# Digital_Io.net
KiCad netlist of a schematic drawn in Altium Designer
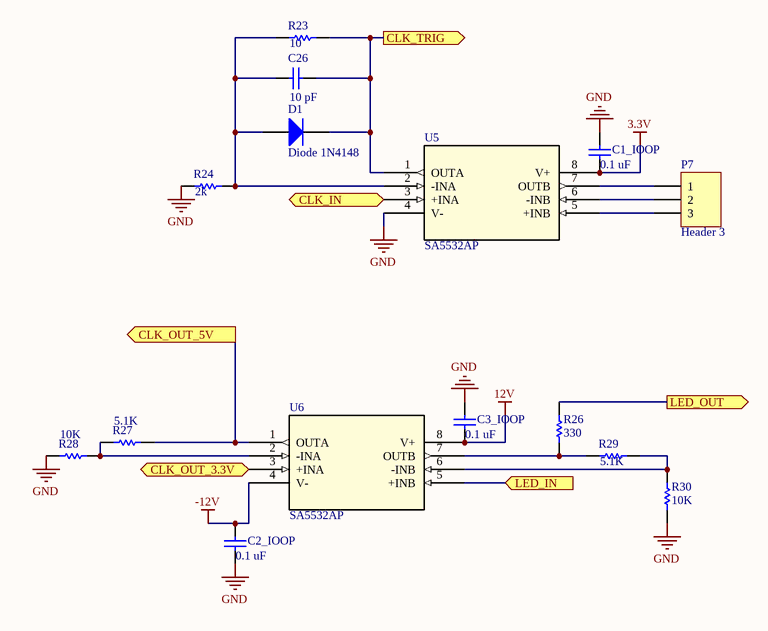
[diagram p0: Digital_Io.SchDoc]

(export (version "E")
  (design (tool "Eeschema 10.0.6"))
  (components
    (comp (ref "C1_IOOP")
      (value "0.1 uF")
      (footprint "C0805")
      (description "Capacitor")
      (fields (field (name "PUBLISHER") "Altium Limited"))
      (libsource (lib "Miscellaneous Devices") (part "Cap"))
    )
    (comp (ref "C2_IOOP")
      (value "0.1 uF")
      (footprint "C0805")
      (description "Capacitor")
      (fields (field (name "PUBLISHER") "Altium Limited"))
      (libsource (lib "Miscellaneous Devices") (part "Cap"))
    )
    (comp (ref "C3_IOOP")
      (value "0.1 uF")
      (footprint "C0805")
      (description "Capacitor")
      (fields (field (name "PUBLISHER") "Altium Limited"))
      (libsource (lib "Miscellaneous Devices") (part "Cap"))
    )
    (comp (ref "C26")
      (value "10 pF")
      (footprint "C0805")
      (description "Capacitor")
      (fields (field (name "PUBLISHER") "Altium Limited"))
      (libsource (lib "Miscellaneous Devices") (part "Cap"))
    )
    (comp (ref "D1")
      (value "Diode 1N4148")
      (footprint "DO-35")
      (description "High Conductance Fast Diode")
      (fields (field (name "PUBLISHER") "Altium Limited"))
      (libsource (lib "Miscellaneous Devices") (part "Diode 1N4148"))
    )
    (comp (ref "P7")
      (value "Header 3")
      (footprint "HDR1X3")
      (description "Header, 3-Pin")
      (fields (field (name "PUBLISHER") "Altium Limited"))
      (libsource (lib "Miscellaneous Connectors") (part "Header 3"))
    )
    (comp (ref "R23")
      (value "10")
      (footprint "AXIAL-0.3")
      (description "Resistor")
      (fields (field (name "Comment") "Res1") (field (name "PUBLISHER") "Altium Limited"))
      (libsource (lib "Miscellaneous Devices") (part "Res1"))
    )
    (comp (ref "R24")
      (value "2k")
      (footprint "AXIAL-0.3")
      (description "Resistor")
      (fields (field (name "Comment") "Res1") (field (name "PUBLISHER") "Altium Limited"))
      (libsource (lib "Miscellaneous Devices") (part "Res1"))
    )
    (comp (ref "R26")
      (value "330")
      (footprint "AXIAL-0.3")
      (description "Resistor")
      (fields (field (name "Comment") "Res1") (field (name "PUBLISHER") "Altium Limited"))
      (libsource (lib "Miscellaneous Devices") (part "Res1"))
    )
    (comp (ref "R27")
      (value "5.1K")
      (footprint "AXIAL-0.3")
      (description "Resistor")
      (fields (field (name "Comment") "Res1") (field (name "PUBLISHER") "Altium Limited"))
      (libsource (lib "Miscellaneous Devices") (part "Res1"))
    )
    (comp (ref "R28")
      (value "10K")
      (footprint "AXIAL-0.3")
      (description "Resistor")
      (fields (field (name "Comment") "Res1") (field (name "PUBLISHER") "Altium Limited"))
      (libsource (lib "Miscellaneous Devices") (part "Res1"))
    )
    (comp (ref "R29")
      (value "5.1K")
      (footprint "AXIAL-0.3")
      (description "Resistor")
      (fields (field (name "Comment") "Res1") (field (name "PUBLISHER") "Altium Limited"))
      (libsource (lib "Miscellaneous Devices") (part "Res1"))
    )
    (comp (ref "R30")
      (value "10K")
      (footprint "AXIAL-0.3")
      (description "Resistor")
      (fields (field (name "Comment") "Res1") (field (name "PUBLISHER") "Altium Limited"))
      (libsource (lib "Miscellaneous Devices") (part "Res1"))
    )
    (comp (ref "U5")
      (value "SA5532AP")
      (footprint "PDIP-8_N")
      (description "Imported")
      (fields
        (field (name "MANUFACTURER_PART_NUMBER") "LT1632CN8#PBF")
        (field (name "DIGIKEYPARTNUMBER") "LT1632CN8-ND")
        (field (name "COPYRIGHT") "Copyright (C) 2015 Accelerated Designs. All rights reserved")
      )
      (libsource (lib "lt1632") (part "LT1632CN8#PBF"))
    )
    (comp (ref "U6")
      (value "SA5532AP")
      (footprint "PDIP-8_N")
      (description "Imported")
      (fields
        (field (name "MANUFACTURER_PART_NUMBER") "LT1632CN8#PBF")
        (field (name "DIGIKEYPARTNUMBER") "LT1632CN8-ND")
        (field (name "COPYRIGHT") "Copyright (C) 2015 Accelerated Designs. All rights reserved")
      )
      (libsource (lib "lt1632") (part "LT1632CN8#PBF"))
    )
  )
  (nets
    (net (code "1") (name "-12V") (class "Default")
      (node (ref "C2_IOOP") (pin "2") (pinfunction "2_2") (pintype "passive"))
      (node (ref "U6") (pin "4") (pinfunction "V-_4") (pintype "power_in"))
    )
    (net (code "2") (name "/CLK_IN") (class "Default")
      (node (ref "U5") (pin "3") (pinfunction "+INA_3") (pintype "input"))
    )
    (net (code "3") (name "/CLK_OUT_3.3V") (class "Default")
      (node (ref "U6") (pin "3") (pinfunction "+INA_3") (pintype "input"))
    )
    (net (code "4") (name "/CLK_OUT_5V") (class "Default")
      (node (ref "R27") (pin "2") (pinfunction "2_2") (pintype "passive"))
      (node (ref "U6") (pin "1") (pinfunction "OUTA_1") (pintype "output"))
    )
    (net (code "5") (name "/CLK_TRIG") (class "Default")
      (node (ref "C26") (pin "1") (pinfunction "1_1") (pintype "passive"))
      (node (ref "D1") (pin "2") (pinfunction "K_2") (pintype "passive"))
      (node (ref "R23") (pin "2") (pinfunction "2_2") (pintype "passive"))
      (node (ref "U5") (pin "1") (pinfunction "OUTA_1") (pintype "output"))
    )
    (net (code "6") (name "/LED_IN") (class "Default")
      (node (ref "U6") (pin "5") (pinfunction "+INB_5") (pintype "input"))
    )
    (net (code "7") (name "/LED_OUT") (class "Default")
      (node (ref "R26") (pin "2") (pinfunction "2_2") (pintype "passive"))
    )
    (net (code "8") (name "3.3V") (class "Default")
      (node (ref "C1_IOOP") (pin "1") (pinfunction "1_1") (pintype "passive"))
      (node (ref "U5") (pin "8") (pinfunction "V+_8") (pintype "power_in"))
    )
    (net (code "9") (name "12V") (class "Default")
      (node (ref "C3_IOOP") (pin "1") (pinfunction "1_1") (pintype "passive"))
      (node (ref "U6") (pin "8") (pinfunction "V+_8") (pintype "power_in"))
    )
    (net (code "10") (name "GND") (class "Default")
      (node (ref "C1_IOOP") (pin "2") (pinfunction "2_2") (pintype "passive"))
      (node (ref "C2_IOOP") (pin "1") (pinfunction "1_1") (pintype "passive"))
      (node (ref "C3_IOOP") (pin "2") (pinfunction "2_2") (pintype "passive"))
      (node (ref "R24") (pin "1") (pinfunction "1_1") (pintype "passive"))
      (node (ref "R28") (pin "1") (pinfunction "1_1") (pintype "passive"))
      (node (ref "R30") (pin "1") (pinfunction "1_1") (pintype "passive"))
      (node (ref "U5") (pin "4") (pinfunction "V-_4") (pintype "power_in"))
    )
    (net (code "11") (name "Net-(D1-A)") (class "Default")
      (node (ref "C26") (pin "2") (pinfunction "2_2") (pintype "passive"))
      (node (ref "D1") (pin "1") (pinfunction "A_1") (pintype "passive"))
      (node (ref "R23") (pin "1") (pinfunction "1_1") (pintype "passive"))
      (node (ref "R24") (pin "2") (pinfunction "2_2") (pintype "passive"))
      (node (ref "U5") (pin "2") (pinfunction "-INA_2") (pintype "input"))
    )
    (net (code "12") (name "Net-(U5-+INB)") (class "Default")
      (node (ref "P7") (pin "3") (pinfunction "3_3") (pintype "passive"))
      (node (ref "U5") (pin "5") (pinfunction "+INB_5") (pintype "input"))
    )
    (net (code "13") (name "Net-(U5--INB)") (class "Default")
      (node (ref "P7") (pin "2") (pinfunction "2_2") (pintype "passive"))
      (node (ref "U5") (pin "6") (pinfunction "-INB_6") (pintype "input"))
    )
    (net (code "14") (name "Net-(U5-OUTB)") (class "Default")
      (node (ref "P7") (pin "1") (pinfunction "1_1") (pintype "passive"))
      (node (ref "U5") (pin "7") (pinfunction "OUTB_7") (pintype "output"))
    )
    (net (code "15") (name "Net-(U6--INA)") (class "Default")
      (node (ref "R27") (pin "1") (pinfunction "1_1") (pintype "passive"))
      (node (ref "R28") (pin "2") (pinfunction "2_2") (pintype "passive"))
      (node (ref "U6") (pin "2") (pinfunction "-INA_2") (pintype "input"))
    )
    (net (code "16") (name "Net-(U6--INB)") (class "Default")
      (node (ref "R29") (pin "2") (pinfunction "2_2") (pintype "passive"))
      (node (ref "R30") (pin "2") (pinfunction "2_2") (pintype "passive"))
      (node (ref "U6") (pin "6") (pinfunction "-INB_6") (pintype "input"))
    )
    (net (code "17") (name "Net-(U6-OUTB)") (class "Default")
      (node (ref "R26") (pin "1") (pinfunction "1_1") (pintype "passive"))
      (node (ref "R29") (pin "1") (pinfunction "1_1") (pintype "passive"))
      (node (ref "U6") (pin "7") (pinfunction "OUTB_7") (pintype "output"))
    )
  )
)
